# Resolver.net
KiCad netlist of a schematic drawn in Altium Designer
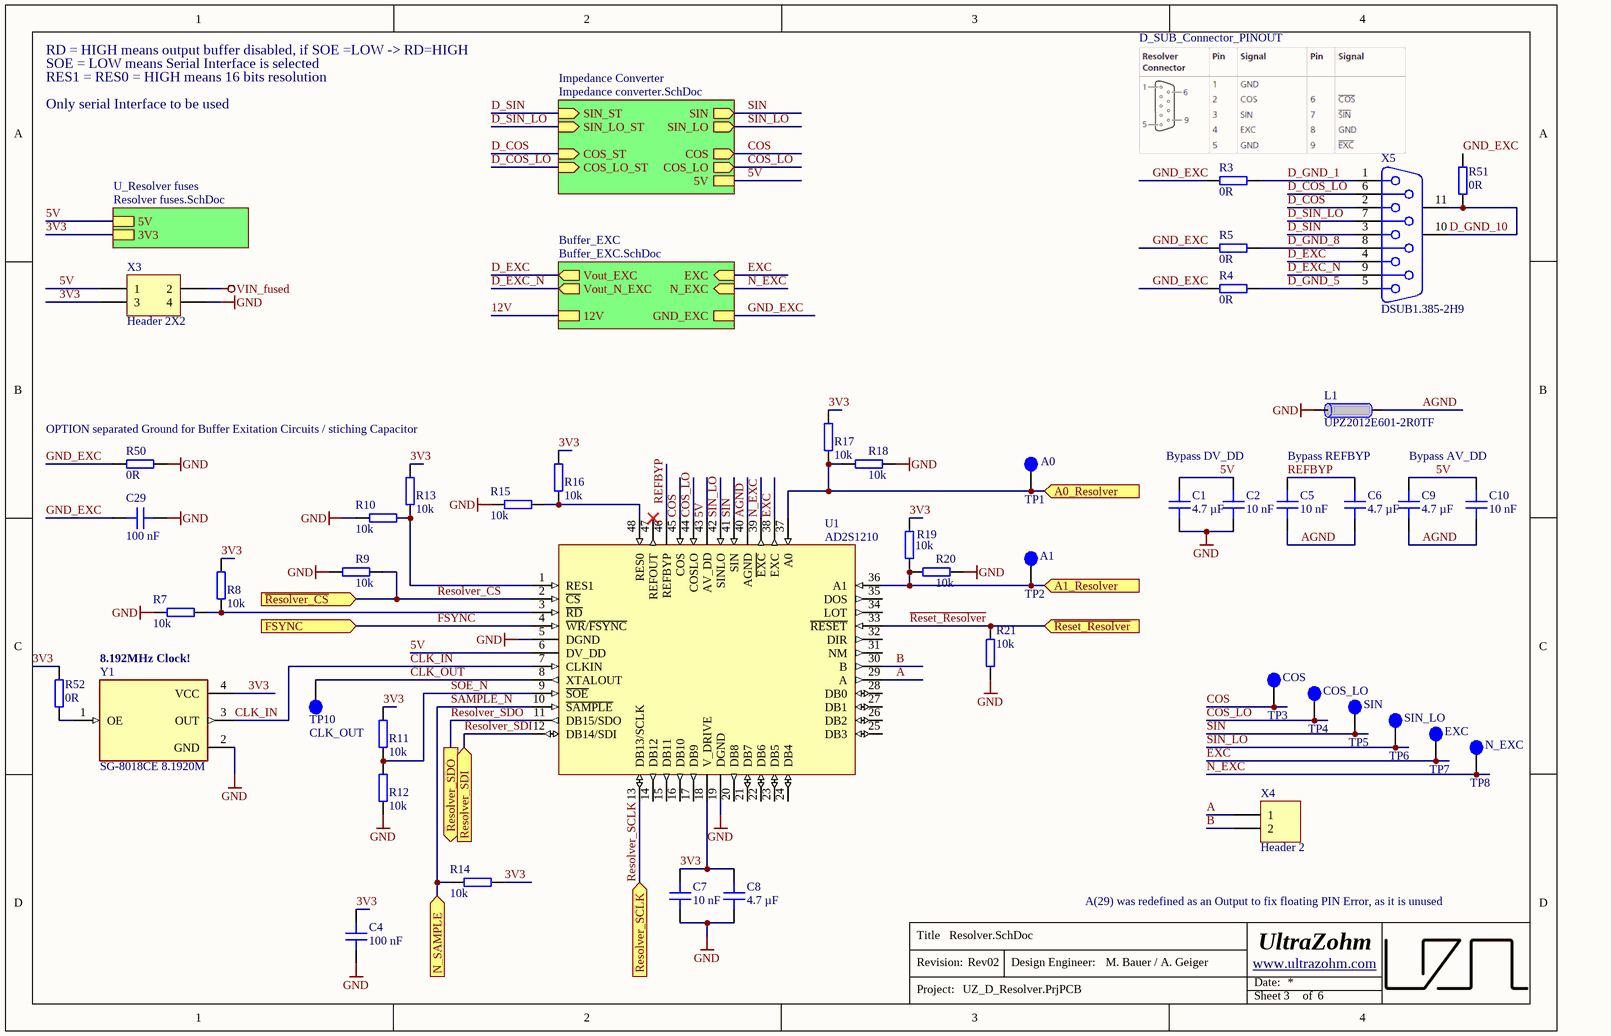
[diagram p0: Resolver.SchDoc]

(export (version "E")
  (design (tool "Eeschema 10.0.6"))
  (components
    (comp (ref "C1")
      (value "4.7 µF")
      (footprint "C_0603")
      (description "Capacitor 0603, 35 VDC, 4.7 µF, X5R")
      (fields
        (field (name "MANUFACTURER PART NUMBER") "GRM188R6YA475KE15D")
        (field (name "MANUFACTURER") "muRata")
        (field (name "CREATED FROM") "MGremer")
      )
      (libsource (lib "user") (part "Capacitor"))
    )
    (comp (ref "C2")
      (value "10 nF")
      (footprint "C_0603")
      (description "50V 10nF X7R ±10% 0603  Multilayer Ceramic Capacitors MLCC - SMD/SMT ROHS")
      (fields
        (field (name "MANUFACTURER PART NUMBER") "0603B103K500NT")
        (field (name "MANUFACTURER") "FH (Guangdong Fenghua Advanced Tech)")
        (field (name "CREATED FROM") "AGeiger")
      )
      (libsource (lib "user") (part "Capacitor"))
    )
    (comp (ref "C4")
      (value "100 nF")
      (footprint "C_0603")
      (description "Capacitor 0603, 50 VDC, 100 nF, X7R")
      (fields
        (field (name "MANUFACTURER PART NUMBER") "CC0603KRX7R9BB104")
        (field (name "MANUFACTURER") "YAGEO")
        (field (name "CREATED FROM") "AGeiger")
      )
      (libsource (lib "user") (part "Capacitor"))
    )
    (comp (ref "C5")
      (value "10 nF")
      (footprint "C_0603")
      (description "50V 10nF X7R ±10% 0603  Multilayer Ceramic Capacitors MLCC - SMD/SMT ROHS")
      (fields
        (field (name "MANUFACTURER PART NUMBER") "0603B103K500NT")
        (field (name "MANUFACTURER") "FH (Guangdong Fenghua Advanced Tech)")
        (field (name "CREATED FROM") "AGeiger")
      )
      (libsource (lib "user") (part "Capacitor"))
    )
    (comp (ref "C6")
      (value "4.7 µF")
      (footprint "C_0603")
      (description "Capacitor 0603, 35 VDC, 4.7 µF, X5R")
      (fields
        (field (name "MANUFACTURER PART NUMBER") "GRM188R6YA475KE15D")
        (field (name "MANUFACTURER") "muRata")
        (field (name "CREATED FROM") "MGremer")
      )
      (libsource (lib "user") (part "Capacitor"))
    )
    (comp (ref "C7")
      (value "10 nF")
      (footprint "C_0603")
      (description "50V 10nF X7R ±10% 0603  Multilayer Ceramic Capacitors MLCC - SMD/SMT ROHS")
      (fields
        (field (name "MANUFACTURER PART NUMBER") "0603B103K500NT")
        (field (name "MANUFACTURER") "FH (Guangdong Fenghua Advanced Tech)")
        (field (name "CREATED FROM") "AGeiger")
      )
      (libsource (lib "user") (part "Capacitor"))
    )
    (comp (ref "C8")
      (value "4.7 µF")
      (footprint "C_0603")
      (description "Capacitor 0603, 35 VDC, 4.7 µF, X5R")
      (fields
        (field (name "MANUFACTURER PART NUMBER") "GRM188R6YA475KE15D")
        (field (name "MANUFACTURER") "muRata")
        (field (name "CREATED FROM") "MGremer")
      )
      (libsource (lib "user") (part "Capacitor"))
    )
    (comp (ref "C9")
      (value "4.7 µF")
      (footprint "C_0603")
      (description "Capacitor 0603, 35 VDC, 4.7 µF, X5R")
      (fields
        (field (name "MANUFACTURER PART NUMBER") "GRM188R6YA475KE15D")
        (field (name "MANUFACTURER") "muRata")
        (field (name "CREATED FROM") "MGremer")
      )
      (libsource (lib "user") (part "Capacitor"))
    )
    (comp (ref "C10")
      (value "10 nF")
      (footprint "C_0603")
      (description "50V 10nF X7R ±10% 0603  Multilayer Ceramic Capacitors MLCC - SMD/SMT ROHS")
      (fields
        (field (name "MANUFACTURER PART NUMBER") "0603B103K500NT")
        (field (name "MANUFACTURER") "FH (Guangdong Fenghua Advanced Tech)")
        (field (name "CREATED FROM") "AGeiger")
      )
      (libsource (lib "user") (part "Capacitor"))
    )
    (comp (ref "C29")
      (value "100 nF")
      (footprint "C_0603")
      (description "Capacitor 0603, 50 VDC, 100 nF, X7R")
      (fields
        (field (name "MANUFACTURER PART NUMBER") "CC0603KRX7R9BB104")
        (field (name "MANUFACTURER") "YAGEO")
        (field (name "CREATED FROM") "AGeiger")
      )
      (libsource (lib "user") (part "Capacitor"))
    )
    (comp (ref "L1")
      (value "UPZ2012E601-2R0TF")
      (footprint "INDC2012X92N_V")
      (description "2A 1 90mΩ 600Ω@100MHz ±25% 0805  Ferrite Beads ROHS")
      (fields
        (field (name "MANUFACTURER") "Sunlord")
        (field (name "LCSC PART NUMBER") "C98308")
        (field (name "CREATED FROM") "AGeiger")
      )
      (libsource (lib "user") (part "Ferrite_Bead"))
    )
    (comp (ref "R3")
      (value "0R")
      (footprint "RES 0603_1608")
      (description "SMD resistor E24 series")
      (fields
        (field (name "MANUFACTURER PART NUMBER") "RC0603JR-070RL")
        (field (name "MANUFACTURER") "YAGEO")
        (field (name "CREATED FROM") "MGremer")
      )
      (libsource (lib "user") (part "Resistor"))
    )
    (comp (ref "R4")
      (value "0R")
      (footprint "RES 0603_1608")
      (description "SMD resistor E24 series")
      (fields
        (field (name "MANUFACTURER PART NUMBER") "RC0603JR-070RL")
        (field (name "MANUFACTURER") "YAGEO")
        (field (name "CREATED FROM") "MGremer")
      )
      (libsource (lib "user") (part "Resistor"))
    )
    (comp (ref "R5")
      (value "0R")
      (footprint "RES 0603_1608")
      (description "SMD resistor E24 series")
      (fields
        (field (name "MANUFACTURER PART NUMBER") "RC0603JR-070RL")
        (field (name "MANUFACTURER") "YAGEO")
        (field (name "CREATED FROM") "MGremer")
      )
      (libsource (lib "user") (part "Resistor"))
    )
    (comp (ref "R7")
      (value "10k")
      (footprint "RES 0603_1608")
      (description "SMD resistor E24 series")
      (fields
        (field (name "MANUFACTURER PART NUMBER") "RK73B1JTTD103J")
        (field (name "MANUFACTURER") "KOA Speer")
        (field (name "CREATED FROM") "MGremer")
      )
      (libsource (lib "user") (part "Resistor"))
    )
    (comp (ref "R8")
      (value "10k")
      (footprint "RES 0603_1608")
      (description "SMD resistor E24 series")
      (fields
        (field (name "MANUFACTURER PART NUMBER") "RK73B1JTTD103J")
        (field (name "MANUFACTURER") "KOA Speer")
        (field (name "CREATED FROM") "MGremer")
      )
      (libsource (lib "user") (part "Resistor"))
    )
    (comp (ref "R9")
      (value "10k")
      (footprint "RES 0603_1608")
      (description "SMD resistor E24 series")
      (fields
        (field (name "MANUFACTURER PART NUMBER") "RK73B1JTTD103J")
        (field (name "MANUFACTURER") "KOA Speer")
        (field (name "CREATED FROM") "MGremer")
      )
      (libsource (lib "user") (part "Resistor"))
    )
    (comp (ref "R10")
      (value "10k")
      (footprint "RES 0603_1608")
      (description "SMD resistor E24 series")
      (fields
        (field (name "MANUFACTURER PART NUMBER") "RK73B1JTTD103J")
        (field (name "MANUFACTURER") "KOA Speer")
        (field (name "CREATED FROM") "MGremer")
      )
      (libsource (lib "user") (part "Resistor"))
    )
    (comp (ref "R11")
      (value "10k")
      (footprint "RES 0603_1608")
      (description "SMD resistor E24 series")
      (fields
        (field (name "MANUFACTURER PART NUMBER") "RK73B1JTTD103J")
        (field (name "MANUFACTURER") "KOA Speer")
        (field (name "CREATED FROM") "MGremer")
      )
      (libsource (lib "user") (part "Resistor"))
    )
    (comp (ref "R12")
      (value "10k")
      (footprint "RES 0603_1608")
      (description "SMD resistor E24 series")
      (fields
        (field (name "MANUFACTURER PART NUMBER") "RK73B1JTTD103J")
        (field (name "MANUFACTURER") "KOA Speer")
        (field (name "CREATED FROM") "MGremer")
      )
      (libsource (lib "user") (part "Resistor"))
    )
    (comp (ref "R13")
      (value "10k")
      (footprint "RES 0603_1608")
      (description "SMD resistor E24 series")
      (fields
        (field (name "MANUFACTURER PART NUMBER") "RK73B1JTTD103J")
        (field (name "MANUFACTURER") "KOA Speer")
        (field (name "CREATED FROM") "MGremer")
      )
      (libsource (lib "user") (part "Resistor"))
    )
    (comp (ref "R14")
      (value "10k")
      (footprint "RES 0603_1608")
      (description "SMD resistor E24 series")
      (fields
        (field (name "MANUFACTURER PART NUMBER") "RK73B1JTTD103J")
        (field (name "MANUFACTURER") "KOA Speer")
        (field (name "CREATED FROM") "MGremer")
      )
      (libsource (lib "user") (part "Resistor"))
    )
    (comp (ref "R15")
      (value "10k")
      (footprint "RES 0603_1608")
      (description "SMD resistor E24 series")
      (fields
        (field (name "MANUFACTURER PART NUMBER") "RK73B1JTTD103J")
        (field (name "MANUFACTURER") "KOA Speer")
        (field (name "CREATED FROM") "MGremer")
      )
      (libsource (lib "user") (part "Resistor"))
    )
    (comp (ref "R16")
      (value "10k")
      (footprint "RES 0603_1608")
      (description "SMD resistor E24 series")
      (fields
        (field (name "MANUFACTURER PART NUMBER") "RK73B1JTTD103J")
        (field (name "MANUFACTURER") "KOA Speer")
        (field (name "CREATED FROM") "MGremer")
      )
      (libsource (lib "user") (part "Resistor"))
    )
    (comp (ref "R17")
      (value "10k")
      (footprint "RES 0603_1608")
      (description "SMD resistor E24 series")
      (fields
        (field (name "MANUFACTURER PART NUMBER") "RK73B1JTTD103J")
        (field (name "MANUFACTURER") "KOA Speer")
        (field (name "CREATED FROM") "MGremer")
      )
      (libsource (lib "user") (part "Resistor"))
    )
    (comp (ref "R18")
      (value "10k")
      (footprint "RES 0603_1608")
      (description "SMD resistor E24 series")
      (fields
        (field (name "MANUFACTURER PART NUMBER") "RK73B1JTTD103J")
        (field (name "MANUFACTURER") "KOA Speer")
        (field (name "CREATED FROM") "MGremer")
      )
      (libsource (lib "user") (part "Resistor"))
    )
    (comp (ref "R19")
      (value "10k")
      (footprint "RES 0603_1608")
      (description "SMD resistor E24 series")
      (fields
        (field (name "MANUFACTURER PART NUMBER") "RK73B1JTTD103J")
        (field (name "MANUFACTURER") "KOA Speer")
        (field (name "CREATED FROM") "MGremer")
      )
      (libsource (lib "user") (part "Resistor"))
    )
    (comp (ref "R20")
      (value "10k")
      (footprint "RES 0603_1608")
      (description "SMD resistor E24 series")
      (fields
        (field (name "MANUFACTURER PART NUMBER") "RK73B1JTTD103J")
        (field (name "MANUFACTURER") "KOA Speer")
        (field (name "CREATED FROM") "MGremer")
      )
      (libsource (lib "user") (part "Resistor"))
    )
    (comp (ref "R21")
      (value "10k")
      (footprint "RES 0603_1608")
      (description "SMD resistor E24 series")
      (fields
        (field (name "MANUFACTURER PART NUMBER") "RK73B1JTTD103J")
        (field (name "MANUFACTURER") "KOA Speer")
        (field (name "CREATED FROM") "MGremer")
      )
      (libsource (lib "user") (part "Resistor"))
    )
    (comp (ref "R50")
      (value "0R")
      (footprint "RES 0603_1608")
      (description "SMD resistor E24 series")
      (fields
        (field (name "MANUFACTURER PART NUMBER") "RC0603JR-070RL")
        (field (name "MANUFACTURER") "YAGEO")
        (field (name "CREATED FROM") "MGremer")
      )
      (libsource (lib "user") (part "Resistor"))
    )
    (comp (ref "R51")
      (value "0R")
      (footprint "RES 0603_1608")
      (description "SMD resistor E24 series")
      (fields
        (field (name "MANUFACTURER PART NUMBER") "RC0603JR-070RL")
        (field (name "MANUFACTURER") "YAGEO")
        (field (name "CREATED FROM") "MGremer")
      )
      (libsource (lib "user") (part "Resistor"))
    )
    (comp (ref "R52")
      (value "0R")
      (footprint "RES 0603_1608")
      (description "SMD resistor E24 series")
      (fields
        (field (name "MANUFACTURER PART NUMBER") "RC0603JR-070RL")
        (field (name "MANUFACTURER") "YAGEO")
        (field (name "CREATED FROM") "MGremer")
      )
      (libsource (lib "user") (part "Resistor"))
    )
    (comp (ref "TP1")
      (value "A0")
      (footprint "TP_1mm")
      (description "Testpoint 1mm")
      (fields (field (name "CREATED") "2018_06_25_AGeiger"))
      (libsource (lib "UltraZOhm_CarrierBoard") (part "TP_1mm"))
    )
    (comp (ref "TP2")
      (value "A1")
      (footprint "TP_1mm")
      (description "Testpoint 1mm")
      (fields (field (name "CREATED") "2018_06_25_AGeiger"))
      (libsource (lib "UltraZOhm_CarrierBoard") (part "TP_1mm"))
    )
    (comp (ref "TP3")
      (value "COS")
      (footprint "TP_1mm")
      (description "Testpoint 1mm")
      (fields (field (name "CREATED") "2018_06_25_AGeiger"))
      (libsource (lib "UltraZOhm_CarrierBoard") (part "TP_1mm"))
    )
    (comp (ref "TP4")
      (value "COS_LO")
      (footprint "TP_1mm")
      (description "Testpoint 1mm")
      (fields (field (name "CREATED") "2018_06_25_AGeiger"))
      (libsource (lib "UltraZOhm_CarrierBoard") (part "TP_1mm"))
    )
    (comp (ref "TP5")
      (value "SIN")
      (footprint "TP_1mm")
      (description "Testpoint 1mm")
      (fields (field (name "CREATED") "2018_06_25_AGeiger"))
      (libsource (lib "UltraZOhm_CarrierBoard") (part "TP_1mm"))
    )
    (comp (ref "TP6")
      (value "SIN_LO")
      (footprint "TP_1mm")
      (description "Testpoint 1mm")
      (fields (field (name "CREATED") "2018_06_25_AGeiger"))
      (libsource (lib "UltraZOhm_CarrierBoard") (part "TP_1mm"))
    )
    (comp (ref "TP7")
      (value "EXC")
      (footprint "TP_1mm")
      (description "Testpoint 1mm")
      (fields (field (name "CREATED") "2018_06_25_AGeiger"))
      (libsource (lib "UltraZOhm_CarrierBoard") (part "TP_1mm"))
    )
    (comp (ref "TP8")
      (value "N_EXC")
      (footprint "TP_1mm")
      (description "Testpoint 1mm")
      (fields (field (name "CREATED") "2018_06_25_AGeiger"))
      (libsource (lib "UltraZOhm_CarrierBoard") (part "TP_1mm"))
    )
    (comp (ref "TP10")
      (value "CLK_OUT")
      (footprint "TP_1mm")
      (description "Testpoint 1mm")
      (fields (field (name "CREATED") "2018_06_25_AGeiger"))
      (libsource (lib "UltraZOhm_CarrierBoard") (part "TP_1mm"))
    )
    (comp (ref "U1")
      (value "AD2S1210")
      (footprint "LQFP-48_L")
      (description "Variable Resolution, 10-Bit to 16-Bit R/D Converter with Reference Oscillator")
      (fields
        (field (name "MF") "Analog Devices")
        (field (name "MPN") "AD2S1210WDSTZRL7")
        (field (name "CREATED") "2019_04_20_AGeiger")
      )
      (libsource (lib "AD_AD2S1210") (part "AD2S1210"))
    )
    (comp (ref "X3")
      (value "Header 2X2")
      (footprint "HDR2X2")
      (description "Header, 2-Pin, Dual row")
      (fields (field (name "PUBLISHER") "Altium Limited"))
      (libsource (lib "Miscellaneous Connectors") (part "Header 2X2"))
    )
    (comp (ref "X4")
      (value "Header 2")
      (footprint "HDR1X2")
      (description "Header, 2-Pin")
      (fields (field (name "PUBLISHER") "Altium Limited"))
      (libsource (lib "Miscellaneous Connectors") (part "Header 2"))
    )
    (comp (ref "X5")
      (value "DSUB1.385-2H9")
      (footprint "DSUB1.385-2H9")
      (description "Connector; D Subminiature; 9 Position; Right Angle; Pitch 1.385 mm")
      (fields
        (field (name "MANUFACTURER") "TE Connectivity")
        (field (name "LCSC PART NUMBER") "C141882")
        (field (name "PUBLISHER") "Altium Limited")
        (field (name "CREATED FROM") "MHlatky")
      )
      (libsource (lib "user") (part "D Connector 9"))
    )
    (comp (ref "Y1")
      (value "SG-8018CE 8.1920M")
      (footprint "OSCCC320X250X120N")
      (description "8.192 MHz XO (Standard) CMOS Oscillator 1.62V ~ 3.63V Enable/Disable 4-SMD, No Lead")
      (fields (field (name "MPN") "SG-8018CE 8.1920M-TJHPA0") (field (name "LCSC PART NUMBER") "C390481"))
      (libsource (lib "SG-8018CE_8.1920M-TJHPA0") (part "SG-8018CE_8.1920M-TJHPA0"))
    )
  )
  (nets
    (net (code "1") (name "/3V3") (class "Default")
      (node (ref "C4") (pin "2") (pinfunction "2_2") (pintype "passive"))
      (node (ref "C7") (pin "2") (pinfunction "2_2") (pintype "passive"))
      (node (ref "C8") (pin "2") (pinfunction "2_2") (pintype "passive"))
      (node (ref "R11") (pin "2") (pinfunction "2_2") (pintype "passive"))
      (node (ref "R13") (pin "2") (pinfunction "2_2") (pintype "passive"))
      (node (ref "R14") (pin "2") (pinfunction "2_2") (pintype "passive"))
      (node (ref "R16") (pin "2") (pinfunction "2_2") (pintype "passive"))
      (node (ref "R17") (pin "2") (pinfunction "2_2") (pintype "passive"))
      (node (ref "R19") (pin "2") (pinfunction "2_2") (pintype "passive"))
      (node (ref "R52") (pin "2") (pinfunction "2_2") (pintype "passive"))
      (node (ref "R8") (pin "2") (pinfunction "2_2") (pintype "passive"))
      (node (ref "U1") (pin "18") (pinfunction "V_DRIVE_18") (pintype "power_in"))
      (node (ref "X3") (pin "3") (pinfunction "3_3") (pintype "passive"))
      (node (ref "Y1") (pin "4") (pinfunction "VCC_4") (pintype "power_in"))
    )
    (net (code "2") (name "/5V") (class "Default")
      (node (ref "C1") (pin "2") (pinfunction "2_2") (pintype "passive"))
      (node (ref "C10") (pin "1") (pinfunction "1_1") (pintype "passive"))
      (node (ref "C2") (pin "2") (pinfunction "2_2") (pintype "passive"))
      (node (ref "C9") (pin "1") (pinfunction "1_1") (pintype "passive"))
      (node (ref "U1") (pin "43") (pinfunction "AV_DD_43") (pintype "power_in"))
      (node (ref "U1") (pin "6") (pinfunction "DV_DD_6") (pintype "power_in"))
      (node (ref "X3") (pin "1") (pinfunction "1_1") (pintype "passive"))
    )
    (net (code "4") (name "/A") (class "Default")
      (node (ref "U1") (pin "29") (pinfunction "A_29") (pintype "output"))
      (node (ref "X4") (pin "1") (pinfunction "1_1") (pintype "passive"))
    )
    (net (code "5") (name "/A0_Resolver") (class "Default")
      (node (ref "R17") (pin "1") (pinfunction "1_1") (pintype "passive"))
      (node (ref "R18") (pin "2") (pinfunction "2_2") (pintype "passive"))
      (node (ref "TP1") (pin "1") (pintype "passive"))
      (node (ref "U1") (pin "37") (pinfunction "A0_37") (pintype "input"))
    )
    (net (code "6") (name "/A1_Resolver") (class "Default")
      (node (ref "R19") (pin "1") (pinfunction "1_1") (pintype "passive"))
      (node (ref "R20") (pin "2") (pinfunction "2_2") (pintype "passive"))
      (node (ref "TP2") (pin "1") (pintype "passive"))
      (node (ref "U1") (pin "36") (pinfunction "A1_36") (pintype "input"))
    )
    (net (code "7") (name "/AGND") (class "Default")
      (node (ref "C10") (pin "2") (pinfunction "2_2") (pintype "passive"))
      (node (ref "C5") (pin "2") (pinfunction "2_2") (pintype "passive"))
      (node (ref "C6") (pin "1") (pinfunction "1_1") (pintype "passive"))
      (node (ref "C9") (pin "2") (pinfunction "2_2") (pintype "passive"))
      (node (ref "L1") (pin "1") (pinfunction "1_1") (pintype "passive"))
      (node (ref "U1") (pin "40") (pinfunction "AGND_40") (pintype "power_in"))
    )
    (net (code "8") (name "/B") (class "Default")
      (node (ref "U1") (pin "30") (pinfunction "B_30") (pintype "output"))
      (node (ref "X4") (pin "2") (pinfunction "2_2") (pintype "passive"))
    )
    (net (code "9") (name "/CLK_IN") (class "Default")
      (node (ref "U1") (pin "7") (pinfunction "CLKIN_7") (pintype "input"))
      (node (ref "Y1") (pin "3") (pinfunction "OUT_3") (pintype "output"))
    )
    (net (code "10") (name "/CLK_OUT") (class "Default")
      (node (ref "TP10") (pin "1") (pintype "passive"))
      (node (ref "U1") (pin "8") (pinfunction "XTALOUT_8") (pintype "output"))
    )
    (net (code "11") (name "/COS") (class "Default")
      (node (ref "TP3") (pin "1") (pintype "passive"))
      (node (ref "U1") (pin "45") (pinfunction "COS_45") (pintype "input"))
    )
    (net (code "12") (name "/COS_LO") (class "Default")
      (node (ref "TP4") (pin "1") (pintype "passive"))
      (node (ref "U1") (pin "44") (pinfunction "COSLO_44") (pintype "input"))
    )
    (net (code "13") (name "/D_COS") (class "Default")
      (node (ref "X5") (pin "2") (pinfunction "2_2") (pintype "passive"))
    )
    (net (code "14") (name "/D_COS_LO") (class "Default")
      (node (ref "X5") (pin "6") (pinfunction "6_6") (pintype "passive"))
    )
    (net (code "15") (name "/D_EXC") (class "Default")
      (node (ref "X5") (pin "4") (pinfunction "4_4") (pintype "passive"))
    )
    (net (code "16") (name "/D_EXC_N") (class "Default")
      (node (ref "X5") (pin "9") (pinfunction "9_9") (pintype "passive"))
    )
    (net (code "17") (name "/D_GND_1") (class "Default")
      (node (ref "R3") (pin "1") (pinfunction "1_1") (pintype "passive"))
      (node (ref "X5") (pin "1") (pinfunction "1_1") (pintype "passive"))
    )
    (net (code "18") (name "/D_GND_5") (class "Default")
      (node (ref "R4") (pin "1") (pinfunction "1_1") (pintype "passive"))
      (node (ref "X5") (pin "5") (pinfunction "5_5") (pintype "passive"))
    )
    (net (code "19") (name "/D_GND_8") (class "Default")
      (node (ref "R5") (pin "1") (pinfunction "1_1") (pintype "passive"))
      (node (ref "X5") (pin "8") (pinfunction "8_8") (pintype "passive"))
    )
    (net (code "20") (name "/D_GND_10") (class "Default")
      (node (ref "R51") (pin "2") (pinfunction "2_2") (pintype "passive"))
      (node (ref "X5") (pin "10") (pinfunction "MH1_10") (pintype "passive"))
      (node (ref "X5") (pin "11") (pinfunction "MH2_11") (pintype "passive"))
    )
    (net (code "21") (name "/D_SIN") (class "Default")
      (node (ref "X5") (pin "3") (pinfunction "3_3") (pintype "passive"))
    )
    (net (code "22") (name "/D_SIN_LO") (class "Default")
      (node (ref "X5") (pin "7") (pinfunction "7_7") (pintype "passive"))
    )
    (net (code "23") (name "/EXC") (class "Default")
      (node (ref "TP7") (pin "1") (pintype "passive"))
      (node (ref "U1") (pin "38") (pinfunction "EXC_38") (pintype "output"))
    )
    (net (code "24") (name "/FSYNC") (class "Default")
      (node (ref "U1") (pin "4") (pinfunction "~{WR}/~{FSYNC}_4") (pintype "input"))
    )
    (net (code "25") (name "/GND_EXC") (class "Default")
      (node (ref "C29") (pin "1") (pinfunction "1_1") (pintype "passive"))
      (node (ref "R3") (pin "2") (pinfunction "2_2") (pintype "passive"))
      (node (ref "R4") (pin "2") (pinfunction "2_2") (pintype "passive"))
      (node (ref "R5") (pin "2") (pinfunction "2_2") (pintype "passive"))
      (node (ref "R50") (pin "1") (pinfunction "1_1") (pintype "passive"))
      (node (ref "R51") (pin "1") (pinfunction "1_1") (pintype "passive"))
    )
    (net (code "26") (name "/N_EXC") (class "Default")
      (node (ref "TP8") (pin "1") (pintype "passive"))
      (node (ref "U1") (pin "39") (pinfunction "~{EXC}_39") (pintype "output"))
    )
    (net (code "27") (name "/REFBYP") (class "Default")
      (node (ref "C5") (pin "1") (pinfunction "1_1") (pintype "passive"))
      (node (ref "C6") (pin "2") (pinfunction "2_2") (pintype "passive"))
      (node (ref "U1") (pin "46") (pinfunction "REFBYP_46") (pintype "passive"))
    )
    (net (code "28") (name "/Reset_Resolver") (class "Default")
      (node (ref "R21") (pin "1") (pinfunction "1_1") (pintype "passive"))
      (node (ref "U1") (pin "33") (pinfunction "~{RESET}_33") (pintype "input"))
    )
    (net (code "29") (name "/Resolver_CS") (class "Default")
      (node (ref "R9") (pin "1") (pinfunction "1_1") (pintype "passive"))
      (node (ref "U1") (pin "2") (pinfunction "~{CS}_2") (pintype "input"))
    )
    (net (code "30") (name "/Resolver_SCLK") (class "Default")
      (node (ref "U1") (pin "13") (pinfunction "DB13/SCLK_13") (pintype "bidirectional"))
    )
    (net (code "31") (name "/Resolver_SDI") (class "Default")
      (node (ref "U1") (pin "12") (pinfunction "DB14/SDI_12") (pintype "bidirectional"))
    )
    (net (code "32") (name "/Resolver_SDO") (class "Default")
      (node (ref "U1") (pin "11") (pinfunction "DB15/SDO_11") (pintype "output"))
    )
    (net (code "33") (name "/SAMPLE_N") (class "Default")
      (node (ref "R14") (pin "1") (pinfunction "1_1") (pintype "passive"))
      (node (ref "U1") (pin "10") (pinfunction "~{SAMPLE}_10") (pintype "input"))
    )
    (net (code "34") (name "/SIN") (class "Default")
      (node (ref "TP5") (pin "1") (pintype "passive"))
      (node (ref "U1") (pin "41") (pinfunction "SIN_41") (pintype "input"))
    )
    (net (code "35") (name "/SIN_LO") (class "Default")
      (node (ref "TP6") (pin "1") (pintype "passive"))
      (node (ref "U1") (pin "42") (pinfunction "SINLO_42") (pintype "input"))
    )
    (net (code "36") (name "/SOE_N") (class "Default")
      (node (ref "R11") (pin "1") (pinfunction "1_1") (pintype "passive"))
      (node (ref "R12") (pin "2") (pinfunction "2_2") (pintype "passive"))
      (node (ref "U1") (pin "9") (pinfunction "~{SOE}_9") (pintype "input"))
    )
    (net (code "37") (name "GND") (class "Default")
      (node (ref "C1") (pin "1") (pinfunction "1_1") (pintype "passive"))
      (node (ref "C2") (pin "1") (pinfunction "1_1") (pintype "passive"))
      (node (ref "C29") (pin "2") (pinfunction "2_2") (pintype "passive"))
      (node (ref "C4") (pin "1") (pinfunction "1_1") (pintype "passive"))
      (node (ref "C7") (pin "1") (pinfunction "1_1") (pintype "passive"))
      (node (ref "C8") (pin "1") (pinfunction "1_1") (pintype "passive"))
      (node (ref "L1") (pin "2") (pinfunction "2_2") (pintype "passive"))
      (node (ref "R10") (pin "1") (pinfunction "1_1") (pintype "passive"))
      (node (ref "R12") (pin "1") (pinfunction "1_1") (pintype "passive"))
      (node (ref "R15") (pin "1") (pinfunction "1_1") (pintype "passive"))
      (node (ref "R18") (pin "1") (pinfunction "1_1") (pintype "passive"))
      (node (ref "R20") (pin "1") (pinfunction "1_1") (pintype "passive"))
      (node (ref "R21") (pin "2") (pinfunction "2_2") (pintype "passive"))
      (node (ref "R50") (pin "2") (pinfunction "2_2") (pintype "passive"))
      (node (ref "R7") (pin "1") (pinfunction "1_1") (pintype "passive"))
      (node (ref "R9") (pin "2") (pinfunction "2_2") (pintype "passive"))
      (node (ref "U1") (pin "19") (pinfunction "DGND_19") (pintype "power_in"))
      (node (ref "U1") (pin "5") (pinfunction "DGND_5") (pintype "power_in"))
      (node (ref "X3") (pin "4") (pinfunction "4_4") (pintype "passive"))
      (node (ref "Y1") (pin "2") (pinfunction "GND_2") (pintype "power_in"))
    )
    (net (code "38") (name "Net-(U1-RES0)") (class "Default")
      (node (ref "R15") (pin "2") (pinfunction "2_2") (pintype "passive"))
      (node (ref "R16") (pin "1") (pinfunction "1_1") (pintype "passive"))
      (node (ref "U1") (pin "48") (pinfunction "RES0_48") (pintype "input"))
    )
    (net (code "39") (name "Net-(U1-RES1)") (class "Default")
      (node (ref "R10") (pin "2") (pinfunction "2_2") (pintype "passive"))
      (node (ref "R13") (pin "1") (pinfunction "1_1") (pintype "passive"))
      (node (ref "U1") (pin "1") (pinfunction "RES1_1") (pintype "input"))
    )
    (net (code "40") (name "Net-(U1-~{RD})") (class "Default")
      (node (ref "R7") (pin "2") (pinfunction "2_2") (pintype "passive"))
      (node (ref "R8") (pin "1") (pinfunction "1_1") (pintype "passive"))
      (node (ref "U1") (pin "3") (pinfunction "~{RD}_3") (pintype "input"))
    )
    (net (code "41") (name "Net-(Y1-OE)") (class "Default")
      (node (ref "R52") (pin "1") (pinfunction "1_1") (pintype "passive"))
      (node (ref "Y1") (pin "1") (pinfunction "OE_1") (pintype "input"))
    )
    (net (code "42") (name "VIN_fused") (class "Default")
      (node (ref "X3") (pin "2") (pinfunction "2_2") (pintype "passive"))
    )
    (net (code "43") (name "unconnected-(U1-DB0-Pad28)") (class "Default")
      (node (ref "U1") (pin "28") (pinfunction "DB0_28") (pintype "bidirectional"))
    )
    (net (code "44") (name "unconnected-(U1-DB1-Pad27)") (class "Default")
      (node (ref "U1") (pin "27") (pinfunction "DB1_27") (pintype "bidirectional"))
    )
    (net (code "45") (name "unconnected-(U1-DB2-Pad26)") (class "Default")
      (node (ref "U1") (pin "26") (pinfunction "DB2_26") (pintype "bidirectional"))
    )
    (net (code "46") (name "unconnected-(U1-DB3-Pad25)") (class "Default")
      (node (ref "U1") (pin "25") (pinfunction "DB3_25") (pintype "bidirectional"))
    )
    (net (code "47") (name "unconnected-(U1-DB4-Pad24)") (class "Default")
      (node (ref "U1") (pin "24") (pinfunction "DB4_24") (pintype "bidirectional"))
    )
    (net (code "48") (name "unconnected-(U1-DB5-Pad23)") (class "Default")
      (node (ref "U1") (pin "23") (pinfunction "DB5_23") (pintype "bidirectional"))
    )
    (net (code "49") (name "unconnected-(U1-DB6-Pad22)") (class "Default")
      (node (ref "U1") (pin "22") (pinfunction "DB6_22") (pintype "bidirectional"))
    )
    (net (code "50") (name "unconnected-(U1-DB7-Pad21)") (class "Default")
      (node (ref "U1") (pin "21") (pinfunction "DB7_21") (pintype "bidirectional"))
    )
    (net (code "51") (name "unconnected-(U1-DB8-Pad20)") (class "Default")
      (node (ref "U1") (pin "20") (pinfunction "DB8_20") (pintype "output"))
    )
    (net (code "52") (name "unconnected-(U1-DB9-Pad17)") (class "Default")
      (node (ref "U1") (pin "17") (pinfunction "DB9_17") (pintype "output"))
    )
    (net (code "53") (name "unconnected-(U1-DB10-Pad16)") (class "Default")
      (node (ref "U1") (pin "16") (pinfunction "DB10_16") (pintype "output"))
    )
    (net (code "54") (name "unconnected-(U1-DB11-Pad15)") (class "Default")
      (node (ref "U1") (pin "15") (pinfunction "DB11_15") (pintype "output"))
    )
    (net (code "55") (name "unconnected-(U1-DB12-Pad14)") (class "Default")
      (node (ref "U1") (pin "14") (pinfunction "DB12_14") (pintype "output"))
    )
    (net (code "56") (name "unconnected-(U1-DIR-Pad32)") (class "Default")
      (node (ref "U1") (pin "32") (pinfunction "DIR_32") (pintype "output"))
    )
    (net (code "57") (name "unconnected-(U1-DOS-Pad35)") (class "Default")
      (node (ref "U1") (pin "35") (pinfunction "DOS_35") (pintype "output"))
    )
    (net (code "58") (name "unconnected-(U1-LOT-Pad34)") (class "Default")
      (node (ref "U1") (pin "34") (pinfunction "LOT_34") (pintype "output"))
    )
    (net (code "59") (name "unconnected-(U1-NM-Pad31)") (class "Default")
      (node (ref "U1") (pin "31") (pinfunction "NM_31") (pintype "output"))
    )
    (net (code "60") (name "unconnected-(U1-REFOUT-Pad47)") (class "Default")
      (node (ref "U1") (pin "47") (pinfunction "REFOUT_47") (pintype "output+no_connect"))
    )
  )
)
